# Sensors11-20.net
KiCad netlist of a schematic drawn in Altium Designer
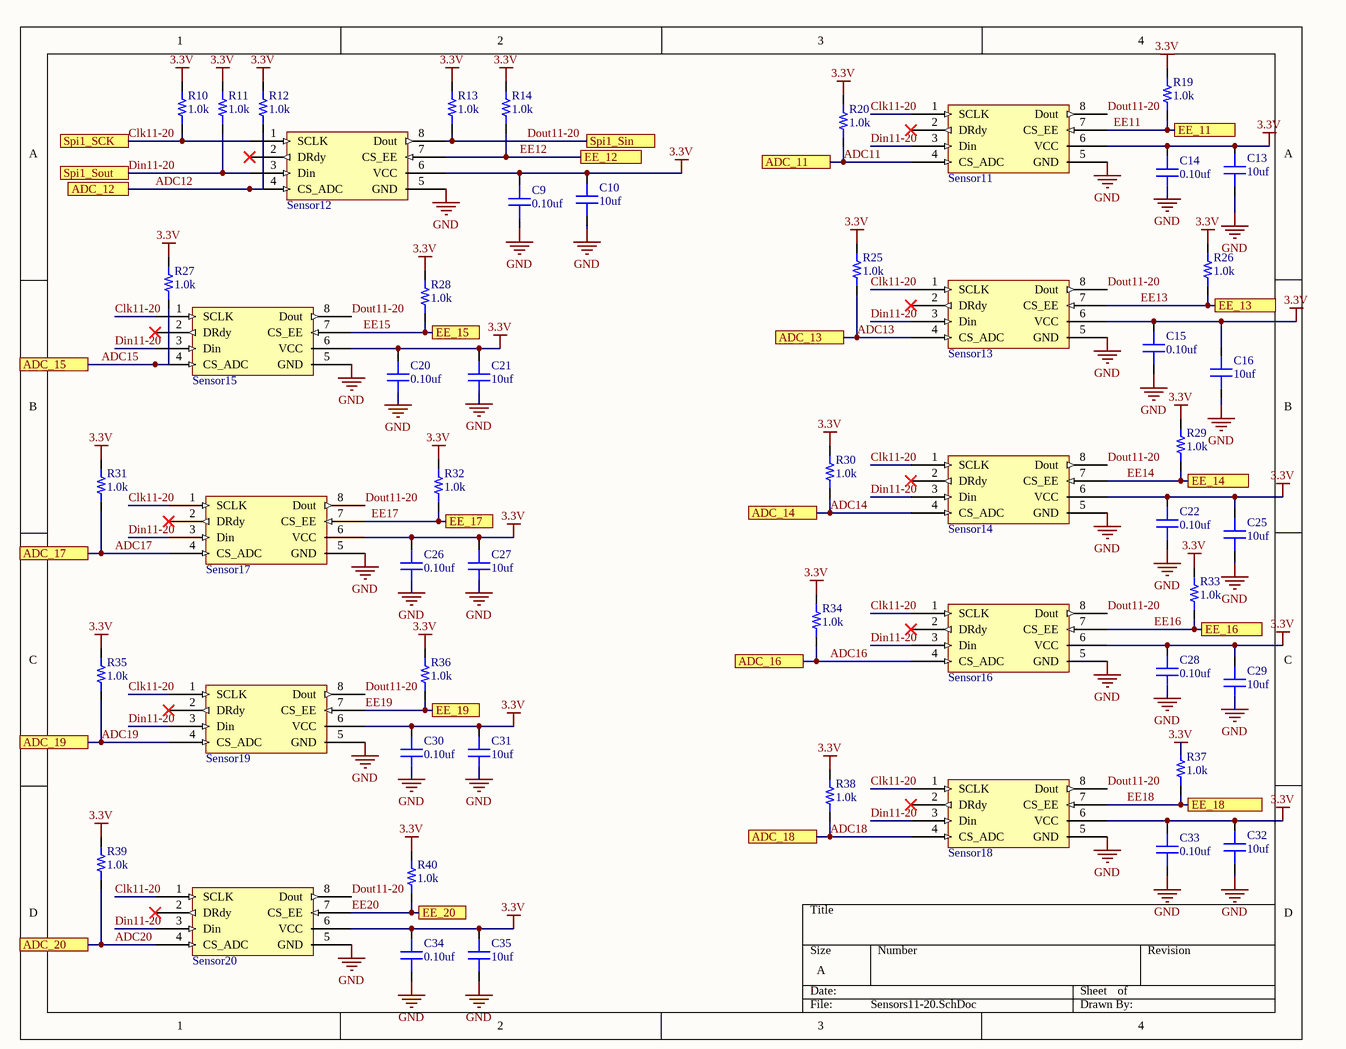
[diagram p0: Sensors11-20.SchDoc]

(export (version "E")
  (design (tool "Eeschema 10.0.6"))
  (components
    (comp (ref "C9")
      (value "0.10uf")
      (footprint "CAP 0603/1608")
      (fields
        (field (name "Comment") "Capacitor MLCC 0.10uf 16V CAP 0603/1608")
        (field (name "CREATED_BY") "Nick Mah")
      )
      (libsource (lib "Altium-Lib") (part "Capacitor"))
    )
    (comp (ref "C10")
      (value "10uf")
      (footprint "CAP 0603/1608")
      (fields
        (field (name "Comment") "Capacitor MLCC 10uf 16V CAP 0603/1608")
        (field (name "CREATED_BY") "Nick Mah")
      )
      (libsource (lib "Altium-Lib") (part "Capacitor"))
    )
    (comp (ref "C13")
      (value "10uf")
      (footprint "CAP 0603/1608")
      (fields
        (field (name "Comment") "Capacitor MLCC 10uf 16V CAP 0603/1608")
        (field (name "CREATED_BY") "Nick Mah")
      )
      (libsource (lib "Altium-Lib") (part "Capacitor"))
    )
    (comp (ref "C14")
      (value "0.10uf")
      (footprint "CAP 0603/1608")
      (fields
        (field (name "Comment") "Capacitor MLCC 0.10uf 16V CAP 0603/1608")
        (field (name "CREATED_BY") "Nick Mah")
      )
      (libsource (lib "Altium-Lib") (part "Capacitor"))
    )
    (comp (ref "C15")
      (value "0.10uf")
      (footprint "CAP 0603/1608")
      (fields
        (field (name "Comment") "Capacitor MLCC 0.10uf 16V CAP 0603/1608")
        (field (name "CREATED_BY") "Nick Mah")
      )
      (libsource (lib "Altium-Lib") (part "Capacitor"))
    )
    (comp (ref "C16")
      (value "10uf")
      (footprint "CAP 0603/1608")
      (fields
        (field (name "Comment") "Capacitor MLCC 10uf 16V CAP 0603/1608")
        (field (name "CREATED_BY") "Nick Mah")
      )
      (libsource (lib "Altium-Lib") (part "Capacitor"))
    )
    (comp (ref "C20")
      (value "0.10uf")
      (footprint "CAP 0603/1608")
      (fields
        (field (name "Comment") "Capacitor MLCC 0.10uf 16V CAP 0603/1608")
        (field (name "CREATED_BY") "Nick Mah")
      )
      (libsource (lib "Altium-Lib") (part "Capacitor"))
    )
    (comp (ref "C21")
      (value "10uf")
      (footprint "CAP 0603/1608")
      (fields
        (field (name "Comment") "Capacitor MLCC 10uf 16V CAP 0603/1608")
        (field (name "CREATED_BY") "Nick Mah")
      )
      (libsource (lib "Altium-Lib") (part "Capacitor"))
    )
    (comp (ref "C22")
      (value "0.10uf")
      (footprint "CAP 0603/1608")
      (fields
        (field (name "Comment") "Capacitor MLCC 0.10uf 16V CAP 0603/1608")
        (field (name "CREATED_BY") "Nick Mah")
      )
      (libsource (lib "Altium-Lib") (part "Capacitor"))
    )
    (comp (ref "C25")
      (value "10uf")
      (footprint "CAP 0603/1608")
      (fields
        (field (name "Comment") "Capacitor MLCC 10uf 16V CAP 0603/1608")
        (field (name "CREATED_BY") "Nick Mah")
      )
      (libsource (lib "Altium-Lib") (part "Capacitor"))
    )
    (comp (ref "C26")
      (value "0.10uf")
      (footprint "CAP 0603/1608")
      (fields
        (field (name "Comment") "Capacitor MLCC 0.10uf 16V CAP 0603/1608")
        (field (name "CREATED_BY") "Nick Mah")
      )
      (libsource (lib "Altium-Lib") (part "Capacitor"))
    )
    (comp (ref "C27")
      (value "10uf")
      (footprint "CAP 0603/1608")
      (fields
        (field (name "Comment") "Capacitor MLCC 10uf 16V CAP 0603/1608")
        (field (name "CREATED_BY") "Nick Mah")
      )
      (libsource (lib "Altium-Lib") (part "Capacitor"))
    )
    (comp (ref "C28")
      (value "0.10uf")
      (footprint "CAP 0603/1608")
      (fields
        (field (name "Comment") "Capacitor MLCC 0.10uf 16V CAP 0603/1608")
        (field (name "CREATED_BY") "Nick Mah")
      )
      (libsource (lib "Altium-Lib") (part "Capacitor"))
    )
    (comp (ref "C29")
      (value "10uf")
      (footprint "CAP 0603/1608")
      (fields
        (field (name "Comment") "Capacitor MLCC 10uf 16V CAP 0603/1608")
        (field (name "CREATED_BY") "Nick Mah")
      )
      (libsource (lib "Altium-Lib") (part "Capacitor"))
    )
    (comp (ref "C30")
      (value "0.10uf")
      (footprint "CAP 0603/1608")
      (fields
        (field (name "Comment") "Capacitor MLCC 0.10uf 16V CAP 0603/1608")
        (field (name "CREATED_BY") "Nick Mah")
      )
      (libsource (lib "Altium-Lib") (part "Capacitor"))
    )
    (comp (ref "C31")
      (value "10uf")
      (footprint "CAP 0603/1608")
      (fields
        (field (name "Comment") "Capacitor MLCC 10uf 16V CAP 0603/1608")
        (field (name "CREATED_BY") "Nick Mah")
      )
      (libsource (lib "Altium-Lib") (part "Capacitor"))
    )
    (comp (ref "C32")
      (value "10uf")
      (footprint "CAP 0603/1608")
      (fields
        (field (name "Comment") "Capacitor MLCC 10uf 16V CAP 0603/1608")
        (field (name "CREATED_BY") "Nick Mah")
      )
      (libsource (lib "Altium-Lib") (part "Capacitor"))
    )
    (comp (ref "C33")
      (value "0.10uf")
      (footprint "CAP 0603/1608")
      (fields
        (field (name "Comment") "Capacitor MLCC 0.10uf 16V CAP 0603/1608")
        (field (name "CREATED_BY") "Nick Mah")
      )
      (libsource (lib "Altium-Lib") (part "Capacitor"))
    )
    (comp (ref "C34")
      (value "0.10uf")
      (footprint "CAP 0603/1608")
      (fields
        (field (name "Comment") "Capacitor MLCC 0.10uf 16V CAP 0603/1608")
        (field (name "CREATED_BY") "Nick Mah")
      )
      (libsource (lib "Altium-Lib") (part "Capacitor"))
    )
    (comp (ref "C35")
      (value "10uf")
      (footprint "CAP 0603/1608")
      (fields
        (field (name "Comment") "Capacitor MLCC 10uf 16V CAP 0603/1608")
        (field (name "CREATED_BY") "Nick Mah")
      )
      (libsource (lib "Altium-Lib") (part "Capacitor"))
    )
    (comp (ref "R10")
      (value "1.0k")
      (footprint "RES 0603/1608")
      (fields
        (field (name "TOLERANCE") "5%")
        (field (name "POWER") "1/10W")
        (field (name "Comment") "Resistor 1.0k 0603 1/10W 5%")
        (field (name "CREATED_BY") "Nick Mah")
      )
      (libsource (lib "Altium-Lib") (part "Resistor"))
    )
    (comp (ref "R11")
      (value "1.0k")
      (footprint "RES 0603/1608")
      (fields
        (field (name "TOLERANCE") "5%")
        (field (name "POWER") "1/10W")
        (field (name "Comment") "Resistor 1.0k 0603 1/10W 5%")
        (field (name "CREATED_BY") "Nick Mah")
      )
      (libsource (lib "Altium-Lib") (part "Resistor"))
    )
    (comp (ref "R12")
      (value "1.0k")
      (footprint "RES 0603/1608")
      (fields
        (field (name "TOLERANCE") "5%")
        (field (name "POWER") "1/10W")
        (field (name "Comment") "Resistor 1.0k 0603 1/10W 5%")
        (field (name "CREATED_BY") "Nick Mah")
      )
      (libsource (lib "Altium-Lib") (part "Resistor"))
    )
    (comp (ref "R13")
      (value "1.0k")
      (footprint "RES 0603/1608")
      (fields
        (field (name "TOLERANCE") "5%")
        (field (name "POWER") "1/10W")
        (field (name "Comment") "Resistor 1.0k 0603 1/10W 5%")
        (field (name "CREATED_BY") "Nick Mah")
      )
      (libsource (lib "Altium-Lib") (part "Resistor"))
    )
    (comp (ref "R14")
      (value "1.0k")
      (footprint "RES 0603/1608")
      (fields
        (field (name "TOLERANCE") "5%")
        (field (name "POWER") "1/10W")
        (field (name "Comment") "Resistor 1.0k 0603 1/10W 5%")
        (field (name "CREATED_BY") "Nick Mah")
      )
      (libsource (lib "Altium-Lib") (part "Resistor"))
    )
    (comp (ref "R19")
      (value "1.0k")
      (footprint "RES 0603/1608")
      (fields
        (field (name "TOLERANCE") "5%")
        (field (name "POWER") "1/10W")
        (field (name "Comment") "Resistor 1.0k 0603 1/10W 5%")
        (field (name "CREATED_BY") "Nick Mah")
      )
      (libsource (lib "Altium-Lib") (part "Resistor"))
    )
    (comp (ref "R20")
      (value "1.0k")
      (footprint "RES 0603/1608")
      (fields
        (field (name "TOLERANCE") "5%")
        (field (name "POWER") "1/10W")
        (field (name "Comment") "Resistor 1.0k 0603 1/10W 5%")
        (field (name "CREATED_BY") "Nick Mah")
      )
      (libsource (lib "Altium-Lib") (part "Resistor"))
    )
    (comp (ref "R25")
      (value "1.0k")
      (footprint "RES 0603/1608")
      (fields
        (field (name "TOLERANCE") "5%")
        (field (name "POWER") "1/10W")
        (field (name "Comment") "Resistor 1.0k 0603 1/10W 5%")
        (field (name "CREATED_BY") "Nick Mah")
      )
      (libsource (lib "Altium-Lib") (part "Resistor"))
    )
    (comp (ref "R26")
      (value "1.0k")
      (footprint "RES 0603/1608")
      (fields
        (field (name "TOLERANCE") "5%")
        (field (name "POWER") "1/10W")
        (field (name "Comment") "Resistor 1.0k 0603 1/10W 5%")
        (field (name "CREATED_BY") "Nick Mah")
      )
      (libsource (lib "Altium-Lib") (part "Resistor"))
    )
    (comp (ref "R27")
      (value "1.0k")
      (footprint "RES 0603/1608")
      (fields
        (field (name "TOLERANCE") "5%")
        (field (name "POWER") "1/10W")
        (field (name "Comment") "Resistor 1.0k 0603 1/10W 5%")
        (field (name "CREATED_BY") "Nick Mah")
      )
      (libsource (lib "Altium-Lib") (part "Resistor"))
    )
    (comp (ref "R28")
      (value "1.0k")
      (footprint "RES 0603/1608")
      (fields
        (field (name "TOLERANCE") "5%")
        (field (name "POWER") "1/10W")
        (field (name "Comment") "Resistor 1.0k 0603 1/10W 5%")
        (field (name "CREATED_BY") "Nick Mah")
      )
      (libsource (lib "Altium-Lib") (part "Resistor"))
    )
    (comp (ref "R29")
      (value "1.0k")
      (footprint "RES 0603/1608")
      (fields
        (field (name "TOLERANCE") "5%")
        (field (name "POWER") "1/10W")
        (field (name "Comment") "Resistor 1.0k 0603 1/10W 5%")
        (field (name "CREATED_BY") "Nick Mah")
      )
      (libsource (lib "Altium-Lib") (part "Resistor"))
    )
    (comp (ref "R30")
      (value "1.0k")
      (footprint "RES 0603/1608")
      (fields
        (field (name "TOLERANCE") "5%")
        (field (name "POWER") "1/10W")
        (field (name "Comment") "Resistor 1.0k 0603 1/10W 5%")
        (field (name "CREATED_BY") "Nick Mah")
      )
      (libsource (lib "Altium-Lib") (part "Resistor"))
    )
    (comp (ref "R31")
      (value "1.0k")
      (footprint "RES 0603/1608")
      (fields
        (field (name "TOLERANCE") "5%")
        (field (name "POWER") "1/10W")
        (field (name "Comment") "Resistor 1.0k 0603 1/10W 5%")
        (field (name "CREATED_BY") "Nick Mah")
      )
      (libsource (lib "Altium-Lib") (part "Resistor"))
    )
    (comp (ref "R32")
      (value "1.0k")
      (footprint "RES 0603/1608")
      (fields
        (field (name "TOLERANCE") "5%")
        (field (name "POWER") "1/10W")
        (field (name "Comment") "Resistor 1.0k 0603 1/10W 5%")
        (field (name "CREATED_BY") "Nick Mah")
      )
      (libsource (lib "Altium-Lib") (part "Resistor"))
    )
    (comp (ref "R33")
      (value "1.0k")
      (footprint "RES 0603/1608")
      (fields
        (field (name "TOLERANCE") "5%")
        (field (name "POWER") "1/10W")
        (field (name "Comment") "Resistor 1.0k 0603 1/10W 5%")
        (field (name "CREATED_BY") "Nick Mah")
      )
      (libsource (lib "Altium-Lib") (part "Resistor"))
    )
    (comp (ref "R34")
      (value "1.0k")
      (footprint "RES 0603/1608")
      (fields
        (field (name "TOLERANCE") "5%")
        (field (name "POWER") "1/10W")
        (field (name "Comment") "Resistor 1.0k 0603 1/10W 5%")
        (field (name "CREATED_BY") "Nick Mah")
      )
      (libsource (lib "Altium-Lib") (part "Resistor"))
    )
    (comp (ref "R35")
      (value "1.0k")
      (footprint "RES 0603/1608")
      (fields
        (field (name "TOLERANCE") "5%")
        (field (name "POWER") "1/10W")
        (field (name "Comment") "Resistor 1.0k 0603 1/10W 5%")
        (field (name "CREATED_BY") "Nick Mah")
      )
      (libsource (lib "Altium-Lib") (part "Resistor"))
    )
    (comp (ref "R36")
      (value "1.0k")
      (footprint "RES 0603/1608")
      (fields
        (field (name "TOLERANCE") "5%")
        (field (name "POWER") "1/10W")
        (field (name "Comment") "Resistor 1.0k 0603 1/10W 5%")
        (field (name "CREATED_BY") "Nick Mah")
      )
      (libsource (lib "Altium-Lib") (part "Resistor"))
    )
    (comp (ref "R37")
      (value "1.0k")
      (footprint "RES 0603/1608")
      (fields
        (field (name "TOLERANCE") "5%")
        (field (name "POWER") "1/10W")
        (field (name "Comment") "Resistor 1.0k 0603 1/10W 5%")
        (field (name "CREATED_BY") "Nick Mah")
      )
      (libsource (lib "Altium-Lib") (part "Resistor"))
    )
    (comp (ref "R38")
      (value "1.0k")
      (footprint "RES 0603/1608")
      (fields
        (field (name "TOLERANCE") "5%")
        (field (name "POWER") "1/10W")
        (field (name "Comment") "Resistor 1.0k 0603 1/10W 5%")
        (field (name "CREATED_BY") "Nick Mah")
      )
      (libsource (lib "Altium-Lib") (part "Resistor"))
    )
    (comp (ref "R39")
      (value "1.0k")
      (footprint "RES 0603/1608")
      (fields
        (field (name "TOLERANCE") "5%")
        (field (name "POWER") "1/10W")
        (field (name "Comment") "Resistor 1.0k 0603 1/10W 5%")
        (field (name "CREATED_BY") "Nick Mah")
      )
      (libsource (lib "Altium-Lib") (part "Resistor"))
    )
    (comp (ref "R40")
      (value "1.0k")
      (footprint "RES 0603/1608")
      (fields
        (field (name "TOLERANCE") "5%")
        (field (name "POWER") "1/10W")
        (field (name "Comment") "Resistor 1.0k 0603 1/10W 5%")
        (field (name "CREATED_BY") "Nick Mah")
      )
      (libsource (lib "Altium-Lib") (part "Resistor"))
    )
    (comp (ref "Sensor11")
      (value "for Aero Pressure Sensor Board")
      (footprint "RSCMJJM005NDSE3 Pressure Sensor")
      (description "RSCMJJM005NDSE3 Pressure Sensor")
      (libsource (lib "Altium-Lib") (part "RSCMJJM005NDSE3 Pressure Sensor"))
    )
    (comp (ref "Sensor12")
      (value "for Aero Pressure Sensor Board")
      (footprint "RSCMJJM005NDSE3 Pressure Sensor")
      (description "RSCMJJM005NDSE3 Pressure Sensor")
      (libsource (lib "Altium-Lib") (part "RSCMJJM005NDSE3 Pressure Sensor"))
    )
    (comp (ref "Sensor13")
      (value "for Aero Pressure Sensor Board")
      (footprint "RSCMJJM005NDSE3 Pressure Sensor")
      (description "RSCMJJM005NDSE3 Pressure Sensor")
      (libsource (lib "Altium-Lib") (part "RSCMJJM005NDSE3 Pressure Sensor"))
    )
    (comp (ref "Sensor14")
      (value "for Aero Pressure Sensor Board")
      (footprint "RSCMJJM005NDSE3 Pressure Sensor")
      (description "RSCMJJM005NDSE3 Pressure Sensor")
      (libsource (lib "Altium-Lib") (part "RSCMJJM005NDSE3 Pressure Sensor"))
    )
    (comp (ref "Sensor15")
      (value "for Aero Pressure Sensor Board")
      (footprint "RSCMJJM005NDSE3 Pressure Sensor")
      (description "RSCMJJM005NDSE3 Pressure Sensor")
      (libsource (lib "Altium-Lib") (part "RSCMJJM005NDSE3 Pressure Sensor"))
    )
    (comp (ref "Sensor16")
      (value "for Aero Pressure Sensor Board")
      (footprint "RSCMJJM005NDSE3 Pressure Sensor")
      (description "RSCMJJM005NDSE3 Pressure Sensor")
      (libsource (lib "Altium-Lib") (part "RSCMJJM005NDSE3 Pressure Sensor"))
    )
    (comp (ref "Sensor17")
      (value "for Aero Pressure Sensor Board")
      (footprint "RSCMJJM005NDSE3 Pressure Sensor")
      (description "RSCMJJM005NDSE3 Pressure Sensor")
      (libsource (lib "Altium-Lib") (part "RSCMJJM005NDSE3 Pressure Sensor"))
    )
    (comp (ref "Sensor18")
      (value "for Aero Pressure Sensor Board")
      (footprint "RSCMJJM005NDSE3 Pressure Sensor")
      (description "RSCMJJM005NDSE3 Pressure Sensor")
      (libsource (lib "Altium-Lib") (part "RSCMJJM005NDSE3 Pressure Sensor"))
    )
    (comp (ref "Sensor19")
      (value "for Aero Pressure Sensor Board")
      (footprint "RSCMJJM005NDSE3 Pressure Sensor")
      (description "RSCMJJM005NDSE3 Pressure Sensor")
      (libsource (lib "Altium-Lib") (part "RSCMJJM005NDSE3 Pressure Sensor"))
    )
    (comp (ref "Sensor20")
      (value "for Aero Pressure Sensor Board")
      (footprint "RSCMJJM005NDSE3 Pressure Sensor")
      (description "RSCMJJM005NDSE3 Pressure Sensor")
      (libsource (lib "Altium-Lib") (part "RSCMJJM005NDSE3 Pressure Sensor"))
    )
  )
  (nets
    (net (code "1") (name "/ADC11") (class "Default")
      (node (ref "R20") (pin "1") (pinfunction "1_1") (pintype "passive"))
      (node (ref "Sensor11") (pin "4") (pinfunction "CS_ADC_4") (pintype "input"))
    )
    (net (code "2") (name "/ADC12") (class "Default")
      (node (ref "R12") (pin "1") (pinfunction "1_1") (pintype "passive"))
      (node (ref "Sensor12") (pin "4") (pinfunction "CS_ADC_4") (pintype "input"))
    )
    (net (code "3") (name "/ADC13") (class "Default")
      (node (ref "R25") (pin "1") (pinfunction "1_1") (pintype "passive"))
      (node (ref "Sensor13") (pin "4") (pinfunction "CS_ADC_4") (pintype "input"))
    )
    (net (code "4") (name "/ADC14") (class "Default")
      (node (ref "R30") (pin "1") (pinfunction "1_1") (pintype "passive"))
      (node (ref "Sensor14") (pin "4") (pinfunction "CS_ADC_4") (pintype "input"))
    )
    (net (code "5") (name "/ADC15") (class "Default")
      (node (ref "R27") (pin "1") (pinfunction "1_1") (pintype "passive"))
      (node (ref "Sensor15") (pin "4") (pinfunction "CS_ADC_4") (pintype "input"))
    )
    (net (code "6") (name "/ADC16") (class "Default")
      (node (ref "R34") (pin "1") (pinfunction "1_1") (pintype "passive"))
      (node (ref "Sensor16") (pin "4") (pinfunction "CS_ADC_4") (pintype "input"))
    )
    (net (code "7") (name "/ADC17") (class "Default")
      (node (ref "R31") (pin "1") (pinfunction "1_1") (pintype "passive"))
      (node (ref "Sensor17") (pin "4") (pinfunction "CS_ADC_4") (pintype "input"))
    )
    (net (code "8") (name "/ADC18") (class "Default")
      (node (ref "R38") (pin "1") (pinfunction "1_1") (pintype "passive"))
      (node (ref "Sensor18") (pin "4") (pinfunction "CS_ADC_4") (pintype "input"))
    )
    (net (code "9") (name "/ADC19") (class "Default")
      (node (ref "R35") (pin "1") (pinfunction "1_1") (pintype "passive"))
      (node (ref "Sensor19") (pin "4") (pinfunction "CS_ADC_4") (pintype "input"))
    )
    (net (code "10") (name "/ADC20") (class "Default")
      (node (ref "R39") (pin "1") (pinfunction "1_1") (pintype "passive"))
      (node (ref "Sensor20") (pin "4") (pinfunction "CS_ADC_4") (pintype "input"))
    )
    (net (code "11") (name "/Clk11-20") (class "Default")
      (node (ref "R10") (pin "1") (pinfunction "1_1") (pintype "passive"))
      (node (ref "Sensor11") (pin "1") (pinfunction "SCLK_1") (pintype "input"))
      (node (ref "Sensor12") (pin "1") (pinfunction "SCLK_1") (pintype "input"))
      (node (ref "Sensor13") (pin "1") (pinfunction "SCLK_1") (pintype "input"))
      (node (ref "Sensor14") (pin "1") (pinfunction "SCLK_1") (pintype "input"))
      (node (ref "Sensor15") (pin "1") (pinfunction "SCLK_1") (pintype "input"))
      (node (ref "Sensor16") (pin "1") (pinfunction "SCLK_1") (pintype "input"))
      (node (ref "Sensor17") (pin "1") (pinfunction "SCLK_1") (pintype "input"))
      (node (ref "Sensor18") (pin "1") (pinfunction "SCLK_1") (pintype "input"))
      (node (ref "Sensor19") (pin "1") (pinfunction "SCLK_1") (pintype "input"))
      (node (ref "Sensor20") (pin "1") (pinfunction "SCLK_1") (pintype "input"))
    )
    (net (code "12") (name "/Din11-20") (class "Default")
      (node (ref "R11") (pin "1") (pinfunction "1_1") (pintype "passive"))
      (node (ref "Sensor11") (pin "3") (pinfunction "Din_3") (pintype "input"))
      (node (ref "Sensor12") (pin "3") (pinfunction "Din_3") (pintype "input"))
      (node (ref "Sensor13") (pin "3") (pinfunction "Din_3") (pintype "input"))
      (node (ref "Sensor14") (pin "3") (pinfunction "Din_3") (pintype "input"))
      (node (ref "Sensor15") (pin "3") (pinfunction "Din_3") (pintype "input"))
      (node (ref "Sensor16") (pin "3") (pinfunction "Din_3") (pintype "input"))
      (node (ref "Sensor17") (pin "3") (pinfunction "Din_3") (pintype "input"))
      (node (ref "Sensor18") (pin "3") (pinfunction "Din_3") (pintype "input"))
      (node (ref "Sensor19") (pin "3") (pinfunction "Din_3") (pintype "input"))
      (node (ref "Sensor20") (pin "3") (pinfunction "Din_3") (pintype "input"))
    )
    (net (code "13") (name "/Dout11-20") (class "Default")
      (node (ref "R13") (pin "1") (pinfunction "1_1") (pintype "passive"))
      (node (ref "Sensor11") (pin "8") (pinfunction "Dout_8") (pintype "output"))
      (node (ref "Sensor12") (pin "8") (pinfunction "Dout_8") (pintype "output"))
      (node (ref "Sensor13") (pin "8") (pinfunction "Dout_8") (pintype "output"))
      (node (ref "Sensor14") (pin "8") (pinfunction "Dout_8") (pintype "output"))
      (node (ref "Sensor15") (pin "8") (pinfunction "Dout_8") (pintype "output"))
      (node (ref "Sensor16") (pin "8") (pinfunction "Dout_8") (pintype "output"))
      (node (ref "Sensor17") (pin "8") (pinfunction "Dout_8") (pintype "output"))
      (node (ref "Sensor18") (pin "8") (pinfunction "Dout_8") (pintype "output"))
      (node (ref "Sensor19") (pin "8") (pinfunction "Dout_8") (pintype "output"))
      (node (ref "Sensor20") (pin "8") (pinfunction "Dout_8") (pintype "output"))
    )
    (net (code "14") (name "/EE11") (class "Default")
      (node (ref "R19") (pin "1") (pinfunction "1_1") (pintype "passive"))
      (node (ref "Sensor11") (pin "7") (pinfunction "CS_EE_7") (pintype "input"))
    )
    (net (code "15") (name "/EE12") (class "Default")
      (node (ref "R14") (pin "1") (pinfunction "1_1") (pintype "passive"))
      (node (ref "Sensor12") (pin "7") (pinfunction "CS_EE_7") (pintype "input"))
    )
    (net (code "16") (name "/EE13") (class "Default")
      (node (ref "R26") (pin "1") (pinfunction "1_1") (pintype "passive"))
      (node (ref "Sensor13") (pin "7") (pinfunction "CS_EE_7") (pintype "input"))
    )
    (net (code "17") (name "/EE14") (class "Default")
      (node (ref "R29") (pin "1") (pinfunction "1_1") (pintype "passive"))
      (node (ref "Sensor14") (pin "7") (pinfunction "CS_EE_7") (pintype "input"))
    )
    (net (code "18") (name "/EE15") (class "Default")
      (node (ref "R28") (pin "1") (pinfunction "1_1") (pintype "passive"))
      (node (ref "Sensor15") (pin "7") (pinfunction "CS_EE_7") (pintype "input"))
    )
    (net (code "19") (name "/EE16") (class "Default")
      (node (ref "R33") (pin "1") (pinfunction "1_1") (pintype "passive"))
      (node (ref "Sensor16") (pin "7") (pinfunction "CS_EE_7") (pintype "input"))
    )
    (net (code "20") (name "/EE17") (class "Default")
      (node (ref "R32") (pin "1") (pinfunction "1_1") (pintype "passive"))
      (node (ref "Sensor17") (pin "7") (pinfunction "CS_EE_7") (pintype "input"))
    )
    (net (code "21") (name "/EE18") (class "Default")
      (node (ref "R37") (pin "1") (pinfunction "1_1") (pintype "passive"))
      (node (ref "Sensor18") (pin "7") (pinfunction "CS_EE_7") (pintype "input"))
    )
    (net (code "22") (name "/EE19") (class "Default")
      (node (ref "R36") (pin "1") (pinfunction "1_1") (pintype "passive"))
      (node (ref "Sensor19") (pin "7") (pinfunction "CS_EE_7") (pintype "input"))
    )
    (net (code "23") (name "/EE20") (class "Default")
      (node (ref "R40") (pin "1") (pinfunction "1_1") (pintype "passive"))
      (node (ref "Sensor20") (pin "7") (pinfunction "CS_EE_7") (pintype "input"))
    )
    (net (code "24") (name "3.3V") (class "Default")
      (node (ref "C10") (pin "2") (pinfunction "2_2") (pintype "passive"))
      (node (ref "C13") (pin "2") (pinfunction "2_2") (pintype "passive"))
      (node (ref "C14") (pin "2") (pinfunction "2_2") (pintype "passive"))
      (node (ref "C15") (pin "2") (pinfunction "2_2") (pintype "passive"))
      (node (ref "C16") (pin "2") (pinfunction "2_2") (pintype "passive"))
      (node (ref "C20") (pin "2") (pinfunction "2_2") (pintype "passive"))
      (node (ref "C21") (pin "2") (pinfunction "2_2") (pintype "passive"))
      (node (ref "C22") (pin "2") (pinfunction "2_2") (pintype "passive"))
      (node (ref "C25") (pin "2") (pinfunction "2_2") (pintype "passive"))
      (node (ref "C26") (pin "2") (pinfunction "2_2") (pintype "passive"))
      (node (ref "C27") (pin "2") (pinfunction "2_2") (pintype "passive"))
      (node (ref "C28") (pin "2") (pinfunction "2_2") (pintype "passive"))
      (node (ref "C29") (pin "2") (pinfunction "2_2") (pintype "passive"))
      (node (ref "C30") (pin "2") (pinfunction "2_2") (pintype "passive"))
      (node (ref "C31") (pin "2") (pinfunction "2_2") (pintype "passive"))
      (node (ref "C32") (pin "2") (pinfunction "2_2") (pintype "passive"))
      (node (ref "C33") (pin "2") (pinfunction "2_2") (pintype "passive"))
      (node (ref "C34") (pin "2") (pinfunction "2_2") (pintype "passive"))
      (node (ref "C35") (pin "2") (pinfunction "2_2") (pintype "passive"))
      (node (ref "C9") (pin "2") (pinfunction "2_2") (pintype "passive"))
      (node (ref "R10") (pin "2") (pinfunction "2_2") (pintype "passive"))
      (node (ref "R11") (pin "2") (pinfunction "2_2") (pintype "passive"))
      (node (ref "R12") (pin "2") (pinfunction "2_2") (pintype "passive"))
      (node (ref "R13") (pin "2") (pinfunction "2_2") (pintype "passive"))
      (node (ref "R14") (pin "2") (pinfunction "2_2") (pintype "passive"))
      (node (ref "R19") (pin "2") (pinfunction "2_2") (pintype "passive"))
      (node (ref "R20") (pin "2") (pinfunction "2_2") (pintype "passive"))
      (node (ref "R25") (pin "2") (pinfunction "2_2") (pintype "passive"))
      (node (ref "R26") (pin "2") (pinfunction "2_2") (pintype "passive"))
      (node (ref "R27") (pin "2") (pinfunction "2_2") (pintype "passive"))
      (node (ref "R28") (pin "2") (pinfunction "2_2") (pintype "passive"))
      (node (ref "R29") (pin "2") (pinfunction "2_2") (pintype "passive"))
      (node (ref "R30") (pin "2") (pinfunction "2_2") (pintype "passive"))
      (node (ref "R31") (pin "2") (pinfunction "2_2") (pintype "passive"))
      (node (ref "R32") (pin "2") (pinfunction "2_2") (pintype "passive"))
      (node (ref "R33") (pin "2") (pinfunction "2_2") (pintype "passive"))
      (node (ref "R34") (pin "2") (pinfunction "2_2") (pintype "passive"))
      (node (ref "R35") (pin "2") (pinfunction "2_2") (pintype "passive"))
      (node (ref "R36") (pin "2") (pinfunction "2_2") (pintype "passive"))
      (node (ref "R37") (pin "2") (pinfunction "2_2") (pintype "passive"))
      (node (ref "R38") (pin "2") (pinfunction "2_2") (pintype "passive"))
      (node (ref "R39") (pin "2") (pinfunction "2_2") (pintype "passive"))
      (node (ref "R40") (pin "2") (pinfunction "2_2") (pintype "passive"))
      (node (ref "Sensor11") (pin "6") (pinfunction "VCC_6") (pintype "power_in"))
      (node (ref "Sensor12") (pin "6") (pinfunction "VCC_6") (pintype "power_in"))
      (node (ref "Sensor13") (pin "6") (pinfunction "VCC_6") (pintype "power_in"))
      (node (ref "Sensor14") (pin "6") (pinfunction "VCC_6") (pintype "power_in"))
      (node (ref "Sensor15") (pin "6") (pinfunction "VCC_6") (pintype "power_in"))
      (node (ref "Sensor16") (pin "6") (pinfunction "VCC_6") (pintype "power_in"))
      (node (ref "Sensor17") (pin "6") (pinfunction "VCC_6") (pintype "power_in"))
      (node (ref "Sensor18") (pin "6") (pinfunction "VCC_6") (pintype "power_in"))
      (node (ref "Sensor19") (pin "6") (pinfunction "VCC_6") (pintype "power_in"))
      (node (ref "Sensor20") (pin "6") (pinfunction "VCC_6") (pintype "power_in"))
    )
    (net (code "25") (name "GND") (class "Default")
      (node (ref "C10") (pin "1") (pinfunction "1_1") (pintype "passive"))
      (node (ref "C13") (pin "1") (pinfunction "1_1") (pintype "passive"))
      (node (ref "C14") (pin "1") (pinfunction "1_1") (pintype "passive"))
      (node (ref "C15") (pin "1") (pinfunction "1_1") (pintype "passive"))
      (node (ref "C16") (pin "1") (pinfunction "1_1") (pintype "passive"))
      (node (ref "C20") (pin "1") (pinfunction "1_1") (pintype "passive"))
      (node (ref "C21") (pin "1") (pinfunction "1_1") (pintype "passive"))
      (node (ref "C22") (pin "1") (pinfunction "1_1") (pintype "passive"))
      (node (ref "C25") (pin "1") (pinfunction "1_1") (pintype "passive"))
      (node (ref "C26") (pin "1") (pinfunction "1_1") (pintype "passive"))
      (node (ref "C27") (pin "1") (pinfunction "1_1") (pintype "passive"))
      (node (ref "C28") (pin "1") (pinfunction "1_1") (pintype "passive"))
      (node (ref "C29") (pin "1") (pinfunction "1_1") (pintype "passive"))
      (node (ref "C30") (pin "1") (pinfunction "1_1") (pintype "passive"))
      (node (ref "C31") (pin "1") (pinfunction "1_1") (pintype "passive"))
      (node (ref "C32") (pin "1") (pinfunction "1_1") (pintype "passive"))
      (node (ref "C33") (pin "1") (pinfunction "1_1") (pintype "passive"))
      (node (ref "C34") (pin "1") (pinfunction "1_1") (pintype "passive"))
      (node (ref "C35") (pin "1") (pinfunction "1_1") (pintype "passive"))
      (node (ref "C9") (pin "1") (pinfunction "1_1") (pintype "passive"))
      (node (ref "Sensor11") (pin "5") (pinfunction "GND_5") (pintype "power_in"))
      (node (ref "Sensor12") (pin "5") (pinfunction "GND_5") (pintype "power_in"))
      (node (ref "Sensor13") (pin "5") (pinfunction "GND_5") (pintype "power_in"))
      (node (ref "Sensor14") (pin "5") (pinfunction "GND_5") (pintype "power_in"))
      (node (ref "Sensor15") (pin "5") (pinfunction "GND_5") (pintype "power_in"))
      (node (ref "Sensor16") (pin "5") (pinfunction "GND_5") (pintype "power_in"))
      (node (ref "Sensor17") (pin "5") (pinfunction "GND_5") (pintype "power_in"))
      (node (ref "Sensor18") (pin "5") (pinfunction "GND_5") (pintype "power_in"))
      (node (ref "Sensor19") (pin "5") (pinfunction "GND_5") (pintype "power_in"))
      (node (ref "Sensor20") (pin "5") (pinfunction "GND_5") (pintype "power_in"))
    )
    (net (code "26") (name "unconnected-(Sensor11-DRdy-Pad2)") (class "Default")
      (node (ref "Sensor11") (pin "2") (pinfunction "DRdy_2") (pintype "output+no_connect"))
    )
    (net (code "27") (name "unconnected-(Sensor12-DRdy-Pad2)") (class "Default")
      (node (ref "Sensor12") (pin "2") (pinfunction "DRdy_2") (pintype "output+no_connect"))
    )
    (net (code "28") (name "unconnected-(Sensor13-DRdy-Pad2)") (class "Default")
      (node (ref "Sensor13") (pin "2") (pinfunction "DRdy_2") (pintype "output+no_connect"))
    )
    (net (code "29") (name "unconnected-(Sensor14-DRdy-Pad2)") (class "Default")
      (node (ref "Sensor14") (pin "2") (pinfunction "DRdy_2") (pintype "output+no_connect"))
    )
    (net (code "30") (name "unconnected-(Sensor15-DRdy-Pad2)") (class "Default")
      (node (ref "Sensor15") (pin "2") (pinfunction "DRdy_2") (pintype "output+no_connect"))
    )
    (net (code "31") (name "unconnected-(Sensor16-DRdy-Pad2)") (class "Default")
      (node (ref "Sensor16") (pin "2") (pinfunction "DRdy_2") (pintype "output+no_connect"))
    )
    (net (code "32") (name "unconnected-(Sensor17-DRdy-Pad2)") (class "Default")
      (node (ref "Sensor17") (pin "2") (pinfunction "DRdy_2") (pintype "output+no_connect"))
    )
    (net (code "33") (name "unconnected-(Sensor18-DRdy-Pad2)") (class "Default")
      (node (ref "Sensor18") (pin "2") (pinfunction "DRdy_2") (pintype "output+no_connect"))
    )
    (net (code "34") (name "unconnected-(Sensor19-DRdy-Pad2)") (class "Default")
      (node (ref "Sensor19") (pin "2") (pinfunction "DRdy_2") (pintype "output+no_connect"))
    )
    (net (code "35") (name "unconnected-(Sensor20-DRdy-Pad2)") (class "Default")
      (node (ref "Sensor20") (pin "2") (pinfunction "DRdy_2") (pintype "output+no_connect"))
    )
  )
)
